# Power.net
KiCad netlist of a schematic drawn in Altium Designer
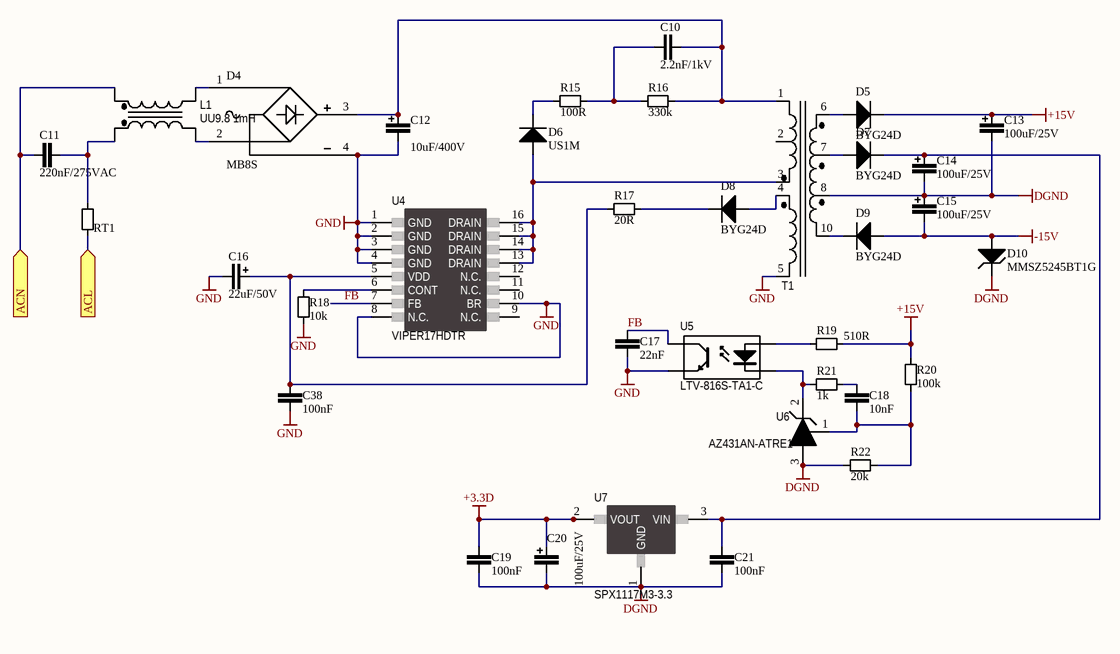
[diagram p0: Power.SchDoc]

(export (version "E")
  (design (tool "Eeschema 10.0.6"))
  (components
    (comp (ref "C10")
      (value "2.2nF/1kV")
      (footprint "GreenBox:1206-C")
      (description "MLCC 2.2nF 10% 1000V X7R 1206")
      (fields (field (name "Comment") "High-Volt Cap") (field (name "PUBLISHER") "GreenBox"))
      (libsource (lib "Capacitor") (part "C21E02N2K3A0"))
    )
    (comp (ref "C11")
      (value "220nF/275VAC")
      (footprint "GreenBox:C-F-C3")
      (description "FILM CAP 220nF 10% 275VAC MPX X2 10mm")
      (fields (field (name "Comment") "FILM Cap") (field (name "PUBLISHER") "GreenBox"))
      (libsource (lib "Capacitor") (part "CXDM220NKAC0"))
    )
    (comp (ref "C12")
      (value "10uF/400V")
      (footprint "GreenBox:C-E-ALU-10X16")
      (description "DIP ECAP 10uF 20% 400V 10X16")
      (fields (field (name "Comment") "ECap") (field (name "PUBLISHER") "GreenBox"))
      (libsource (lib "Capacitor") (part "C3AE010UM2G0"))
    )
    (comp (ref "C13")
      (value "100uF/25V")
      (footprint "GreenBox:C-E-ALU-6.3X11.5")
      (description "DIP ECAP 100uF 20% 25V 6.3X11.5")
      (fields (field (name "Comment") "ECap") (field (name "PUBLISHER") "GreenBox"))
      (libsource (lib "Capacitor") (part "C3AC100UM1E0"))
    )
    (comp (ref "C14")
      (value "100uF/25V")
      (footprint "GreenBox:C-E-ALU-6.3X11.5")
      (description "DIP ECAP 100uF 20% 25V 6.3X11.5")
      (fields (field (name "Comment") "ECap") (field (name "PUBLISHER") "GreenBox"))
      (libsource (lib "Capacitor") (part "C3AC100UM1E0"))
    )
    (comp (ref "C15")
      (value "100uF/25V")
      (footprint "GreenBox:C-E-ALU-6.3X11.5")
      (description "DIP ECAP 100uF 20% 25V 6.3X11.5")
      (fields (field (name "Comment") "ECap") (field (name "PUBLISHER") "GreenBox"))
      (libsource (lib "Capacitor") (part "C3AC100UM1E0"))
    )
    (comp (ref "C16")
      (value "22uF/50V")
      (footprint "GreenBox:C-E-ALU-5X11")
      (description "DIP ECAP 22uF 20% 50V 5X11")
      (fields (field (name "Comment") "ECap") (field (name "PUBLISHER") "GreenBox"))
      (libsource (lib "Capacitor") (part "C3AB022UM1H0"))
    )
    (comp (ref "C17")
      (value "22nF")
      (footprint "GreenBox:0603-C")
      (description "MLCC 22nF 10% 50V X7R 0603")
      (fields (field (name "Comment") "Cap") (field (name "PUBLISHER") "GreenBox"))
      (libsource (lib "Capacitor") (part "C21C022NK1H0"))
    )
    (comp (ref "C18")
      (value "10nF")
      (footprint "GreenBox:0603-C")
      (description "MLCC 10nF 10% 50V X7R 0603")
      (fields (field (name "Comment") "Cap") (field (name "PUBLISHER") "GreenBox"))
      (libsource (lib "Capacitor") (part "C21C010NK1H0"))
    )
    (comp (ref "C19")
      (value "100nF")
      (footprint "GreenBox:0603-C")
      (description "MLCC 100nF 10% 50V X7R 0603")
      (fields (field (name "Comment") "Cap") (field (name "PUBLISHER") "GreenBox"))
      (libsource (lib "Capacitor") (part "C21C100NK1H0"))
    )
    (comp (ref "C20")
      (value "100uF/25V")
      (footprint "GreenBox:C-E-ALU-6.3X11.5")
      (description "DIP ECAP 100uF 20% 25V 6.3X11.5")
      (fields (field (name "Comment") "ECap") (field (name "PUBLISHER") "GreenBox"))
      (libsource (lib "Capacitor") (part "C3AC100UM1E0"))
    )
    (comp (ref "C21")
      (value "100nF")
      (footprint "GreenBox:0603-C")
      (description "MLCC 100nF 10% 50V X7R 0603")
      (fields (field (name "Comment") "Cap") (field (name "PUBLISHER") "GreenBox"))
      (libsource (lib "Capacitor") (part "C21C100NK1H0"))
    )
    (comp (ref "C38")
      (value "100nF")
      (footprint "GreenBox:0603-C")
      (description "MLCC 100nF 10% 50V X7R 0603")
      (fields (field (name "Comment") "Cap") (field (name "PUBLISHER") "GreenBox"))
      (libsource (lib "Capacitor") (part "C21C100NK1H0"))
    )
    (comp (ref "D4")
      (value "MB8S")
      (footprint "GreenBox:MBS-1")
      (description "Bridge Rectifiers MB8S 800V 0.5A")
      (fields (field (name "MANUFACTURER") "ON SEMICONDUCTOR") (field (name "PUBLISHER") "GreenBox"))
      (libsource (lib "Diode_Transistor") (part "DBSAMB8S0000"))
    )
    (comp (ref "D5")
      (value "BYG24D")
      (footprint "GreenBox:DO-214AC")
      (description "Fast Recovery Rectifiers BYG24D Vrrm 200V If 1.5A 140nS")
      (fields (field (name "MANUFACTURER") "VISHAY") (field (name "PUBLISHER") "GreenBox"))
      (libsource (lib "Diode_Transistor") (part "D461BYG24D0V"))
    )
    (comp (ref "D6")
      (value "US1M")
      (footprint "GreenBox:DO-214AC")
      (description "Fast Recovery Rectifiers US1M Vrrm 1000V If 1A 75nS")
      (fields (field (name "PUBLISHER") "GreenBox"))
      (libsource (lib "Diode_Transistor") (part "D461US1M0000"))
    )
    (comp (ref "D7")
      (value "BYG24D")
      (footprint "GreenBox:DO-214AC")
      (description "Fast Recovery Rectifiers BYG24D Vrrm 200V If 1.5A 140nS")
      (fields (field (name "MANUFACTURER") "VISHAY") (field (name "PUBLISHER") "GreenBox"))
      (libsource (lib "Diode_Transistor") (part "D461BYG24D0V"))
    )
    (comp (ref "D8")
      (value "BYG24D")
      (footprint "GreenBox:DO-214AC")
      (description "Fast Recovery Rectifiers BYG24D Vrrm 200V If 1.5A 140nS")
      (fields (field (name "MANUFACTURER") "VISHAY") (field (name "PUBLISHER") "GreenBox"))
      (libsource (lib "Diode_Transistor") (part "D461BYG24D0V"))
    )
    (comp (ref "D9")
      (value "BYG24D")
      (footprint "GreenBox:DO-214AC")
      (description "Fast Recovery Rectifiers BYG24D Vrrm 200V If 1.5A 140nS")
      (fields (field (name "MANUFACTURER") "VISHAY") (field (name "PUBLISHER") "GreenBox"))
      (libsource (lib "Diode_Transistor") (part "D461BYG24D0V"))
    )
    (comp (ref "D10")
      (value "MMSZ5245BT1G")
      (footprint "GreenBox:SOD-123")
      (description "Zener Voltage Regulators MMSZ5245BT1G 15V 0W5")
      (fields (field (name "MANUFACTURER") "ON SEMICONDUCTOR") (field (name "PUBLISHER") "GreenBox"))
      (libsource (lib "Diode_Transistor") (part "D531MSZ5245O"))
    )
    (comp (ref "L1")
      (value "UU9.8 1mH")
      (footprint "GreenBox:UU9_8")
      (description "Common Mode Inductor UU9.8 1mH 1A")
      (fields (field (name "PUBLISHER") "GreenBox"))
      (libsource (lib "Inductor") (part "LCDZUU9801M0"))
    )
    (comp (ref "R15")
      (value "100R")
      (footprint "GreenBox:1206-R")
      (description "SMD Resistor 100R 1% 1/4W 1206 100PPM")
      (fields (field (name "Comment") "Res") (field (name "PUBLISHER") "GreenBox"))
      (libsource (lib "Resistor") (part "R11E100RFDF0"))
    )
    (comp (ref "R16")
      (value "330k")
      (footprint "GreenBox:1206-R")
      (description "SMD Resistor 330k 1% 1/4W 1206 100PPM")
      (fields (field (name "Comment") "Res") (field (name "PUBLISHER") "GreenBox"))
      (libsource (lib "Resistor") (part "R11E330KFDF0"))
    )
    (comp (ref "R17")
      (value "20R")
      (footprint "GreenBox:1206-R")
      (description "SMD Resistor 20R 1% 1/4W 1206 100PPM")
      (fields (field (name "Comment") "Res") (field (name "PUBLISHER") "GreenBox"))
      (libsource (lib "Resistor") (part "R11E020RFDF0"))
    )
    (comp (ref "R18")
      (value "10k")
      (footprint "GreenBox:0603-R")
      (description "SMD Resistor 10k 1% 1/10W 0603 100PPM")
      (fields (field (name "Comment") "Res") (field (name "PUBLISHER") "GreenBox"))
      (libsource (lib "Resistor") (part "R11C010KFBF0"))
    )
    (comp (ref "R19")
      (value "510R")
      (footprint "GreenBox:0603-R")
      (description "SMD Resistor 510R 1% 1/10W 0603 100PPM")
      (fields (field (name "Comment") "Res") (field (name "PUBLISHER") "GreenBox"))
      (libsource (lib "Resistor") (part "R11C510RFBF0"))
    )
    (comp (ref "R20")
      (value "100k")
      (footprint "GreenBox:0603-R")
      (description "SMD Resistor 100k 1% 1/10W 0603 100PPM")
      (fields (field (name "Comment") "Res") (field (name "PUBLISHER") "GreenBox"))
      (libsource (lib "Resistor") (part "R11C100KFBF0"))
    )
    (comp (ref "R21")
      (value "1k")
      (footprint "GreenBox:0603-R")
      (description "SMD Resistor 1k 1% 1/10W 0603 100PPM")
      (fields (field (name "Comment") "Res") (field (name "PUBLISHER") "GreenBox"))
      (libsource (lib "Resistor") (part "R11C001KFBF0"))
    )
    (comp (ref "R22")
      (value "20k")
      (footprint "GreenBox:0603-R")
      (description "SMD Resistor 20k 1% 1/10W 0603 100PPM")
      (fields (field (name "Comment") "Res") (field (name "PUBLISHER") "GreenBox"))
      (libsource (lib "Resistor") (part "R11C020KFBF0"))
    )
    (comp (ref "RT1")
      (value "SY16P")
      (footprint "GreenBox:PTC-16P")
      (description "PTC SY16P")
      (fields (field (name "PUBLISHER") "GreenBox"))
      (libsource (lib "Resistor") (part "RPDZSY16P000"))
    )
    (comp (ref "T1")
      (value "Transformer")
      (footprint "GreenBox:EE13-5+5-Q9")
      (description "Transformer EE13 GREENBOX 16A Auxiliary Power")
      (fields (field (name "PUBLISHER") "GreenBox"))
      (libsource (lib "Transformer") (part "MTD5220050A0"))
    )
    (comp (ref "U4")
      (value "VIPER17HDTR")
      (footprint "GreenBox:SO-16_N")
      (description "Switching Regulator VIPER17HDTR 127kHz")
      (fields (field (name "MANUFACTURER") "STMicroelectronics") (field (name "PUBLISHER") "GreenBox"))
      (libsource (lib "DCDC_LDO") (part "UDS3VIPER17S"))
    )
    (comp (ref "U5")
      (value "LTV-816S-TA1-C")
      (footprint "GreenBox:DIP-4-SMD-OPTO")
      (description "Phototransistor Optocoupler LTV-816S-TA1-C Viso 5000Vrms")
      (fields (field (name "MANUFACTURER") "LITE-ON ELECTRONICS") (field (name "PUBLISHER") "GreenBox"))
      (libsource (lib "Optocoupler") (part "UOSBLTV816SI"))
    )
    (comp (ref "U6")
      (value "AZ431AN-ATRE1")
      (footprint "GreenBox:SOT-23_N")
      (description "Voltage Reference AZ431AN-ATRE1 Vref 2.5V")
      (fields (field (name "MANUFACTURER") "BCD SEMICONDUCTOR") (field (name "PUBLISHER") "GreenBox"))
      (libsource (lib "DCDC_LDO") (part "UV42AZ431ANB"))
    )
    (comp (ref "U7")
      (value "SPX1117M3-3.3")
      (footprint "GreenBox:SOT223_N")
      (description "LDO SPX1117M3-3.3 3V3 800mA")
      (fields (field (name "MANUFACTURER") "SIPEX CORPORATION") (field (name "PUBLISHER") "GreenBox"))
      (libsource (lib "DCDC_LDO") (part "UL4111173V3E"))
    )
  )
  (nets
    (net (code "1") (name "+3.3D") (class "Default")
      (node (ref "C19") (pin "1") (pinfunction "1_1") (pintype "passive"))
      (node (ref "C20") (pin "1") (pinfunction "1_1") (pintype "passive"))
      (node (ref "U7") (pin "2") (pinfunction "VOUT_2") (pintype "passive"))
      (node (ref "U7") (pin "4") (pinfunction "VOUT_4") (pintype "passive"))
    )
    (net (code "2") (name "+15V") (class "Default")
      (node (ref "C13") (pin "1") (pinfunction "1_1") (pintype "passive"))
      (node (ref "D5") (pin "2") (pinfunction "K_2") (pintype "passive"))
      (node (ref "R19") (pin "1") (pinfunction "1_1") (pintype "passive"))
      (node (ref "R20") (pin "2") (pinfunction "2_2") (pintype "passive"))
    )
    (net (code "3") (name "-15V") (class "Default")
      (node (ref "C15") (pin "2") (pinfunction "2_2") (pintype "passive"))
      (node (ref "D10") (pin "1") (pinfunction "A_1") (pintype "passive"))
      (node (ref "D9") (pin "1") (pinfunction "A_1") (pintype "passive"))
    )
    (net (code "4") (name "/ACL") (class "Default")
      (node (ref "RT1") (pin "1") (pinfunction "1_1") (pintype "passive"))
    )
    (net (code "5") (name "/ACN") (class "Default")
      (node (ref "C11") (pin "1") (pinfunction "1_1") (pintype "passive"))
      (node (ref "L1") (pin "3") (pinfunction "Sec+_3") (pintype "passive"))
    )
    (net (code "6") (name "/FB") (class "Default")
      (node (ref "C17") (pin "1") (pinfunction "1_1") (pintype "passive"))
      (node (ref "U4") (pin "7") (pinfunction "FB_7") (pintype "passive"))
      (node (ref "U5") (pin "4") (pinfunction "C_4") (pintype "passive"))
    )
    (net (code "7") (name "DGND") (class "Default")
      (node (ref "C13") (pin "2") (pinfunction "2_2") (pintype "passive"))
      (node (ref "C14") (pin "2") (pinfunction "2_2") (pintype "passive"))
      (node (ref "C15") (pin "1") (pinfunction "1_1") (pintype "passive"))
      (node (ref "C19") (pin "2") (pinfunction "2_2") (pintype "passive"))
      (node (ref "C20") (pin "2") (pinfunction "2_2") (pintype "passive"))
      (node (ref "C21") (pin "1") (pinfunction "1_1") (pintype "passive"))
      (node (ref "D10") (pin "2") (pinfunction "K_2") (pintype "passive"))
      (node (ref "R22") (pin "2") (pinfunction "2_2") (pintype "passive"))
      (node (ref "T1") (pin "8") (pinfunction "8_8") (pintype "passive"))
      (node (ref "U6") (pin "3") (pinfunction "IN-_3") (pintype "passive"))
      (node (ref "U7") (pin "1") (pinfunction "GND_1") (pintype "passive"))
    )
    (net (code "8") (name "GND") (class "Default")
      (node (ref "C12") (pin "2") (pinfunction "2_2") (pintype "passive"))
      (node (ref "C16") (pin "2") (pinfunction "2_2") (pintype "passive"))
      (node (ref "C17") (pin "2") (pinfunction "2_2") (pintype "passive"))
      (node (ref "C38") (pin "2") (pinfunction "2_2") (pintype "passive"))
      (node (ref "D4") (pin "4") (pinfunction "-_4") (pintype "passive"))
      (node (ref "R18") (pin "2") (pinfunction "2_2") (pintype "passive"))
      (node (ref "T1") (pin "5") (pinfunction "5_5") (pintype "passive"))
      (node (ref "U4") (pin "1") (pinfunction "GND_1") (pintype "passive"))
      (node (ref "U4") (pin "10") (pinfunction "BR_10") (pintype "passive"))
      (node (ref "U4") (pin "2") (pinfunction "GND_2") (pintype "passive"))
      (node (ref "U4") (pin "3") (pinfunction "GND_3") (pintype "passive"))
      (node (ref "U4") (pin "4") (pinfunction "GND_4") (pintype "passive"))
      (node (ref "U4") (pin "8") (pinfunction "N.C._8") (pintype "passive"))
      (node (ref "U5") (pin "3") (pinfunction "E_3") (pintype "passive"))
    )
    (net (code "9") (name "Net-(C10-Pad1)") (class "Default")
      (node (ref "C10") (pin "1") (pinfunction "1_1") (pintype "passive"))
      (node (ref "R15") (pin "2") (pinfunction "2_2") (pintype "passive"))
      (node (ref "R16") (pin "2") (pinfunction "2_2") (pintype "passive"))
    )
    (net (code "10") (name "Net-(C18-Pad1)") (class "Default")
      (node (ref "C18") (pin "1") (pinfunction "1_1") (pintype "passive"))
      (node (ref "R21") (pin "2") (pinfunction "2_2") (pintype "passive"))
    )
    (net (code "11") (name "Net-(D4-+)") (class "Default")
      (node (ref "C10") (pin "2") (pinfunction "2_2") (pintype "passive"))
      (node (ref "C12") (pin "1") (pinfunction "1_1") (pintype "passive"))
      (node (ref "D4") (pin "3") (pinfunction "+_3") (pintype "passive"))
      (node (ref "R16") (pin "1") (pinfunction "1_1") (pintype "passive"))
      (node (ref "T1") (pin "1") (pinfunction "1_1") (pintype "passive"))
    )
    (net (code "12") (name "Net-(D5-A)") (class "Default")
      (node (ref "D5") (pin "1") (pinfunction "A_1") (pintype "passive"))
      (node (ref "T1") (pin "6") (pinfunction "6_6") (pintype "passive"))
    )
    (net (code "13") (name "Net-(D6-A)") (class "Default")
      (node (ref "D6") (pin "1") (pinfunction "A_1") (pintype "passive"))
      (node (ref "T1") (pin "3") (pinfunction "3_3") (pintype "passive"))
      (node (ref "U4") (pin "13") (pinfunction "DRAIN_13") (pintype "passive"))
      (node (ref "U4") (pin "14") (pinfunction "DRAIN_14") (pintype "passive"))
      (node (ref "U4") (pin "15") (pinfunction "DRAIN_15") (pintype "passive"))
      (node (ref "U4") (pin "16") (pinfunction "DRAIN_16") (pintype "passive"))
    )
    (net (code "14") (name "Net-(D6-K)") (class "Default")
      (node (ref "D6") (pin "2") (pinfunction "K_2") (pintype "passive"))
      (node (ref "R15") (pin "1") (pinfunction "1_1") (pintype "passive"))
    )
    (net (code "15") (name "Net-(D7-A)") (class "Default")
      (node (ref "D7") (pin "1") (pinfunction "A_1") (pintype "passive"))
      (node (ref "T1") (pin "7") (pinfunction "7_7") (pintype "passive"))
    )
    (net (code "16") (name "Net-(D7-K)") (class "Default")
      (node (ref "C14") (pin "1") (pinfunction "1_1") (pintype "passive"))
      (node (ref "C21") (pin "2") (pinfunction "2_2") (pintype "passive"))
      (node (ref "D7") (pin "2") (pinfunction "K_2") (pintype "passive"))
      (node (ref "U7") (pin "3") (pinfunction "VIN_3") (pintype "passive"))
    )
    (net (code "17") (name "Net-(D8-A)") (class "Default")
      (node (ref "D8") (pin "1") (pinfunction "A_1") (pintype "passive"))
      (node (ref "T1") (pin "4") (pinfunction "4_4") (pintype "passive"))
    )
    (net (code "18") (name "Net-(D8-K)") (class "Default")
      (node (ref "D8") (pin "2") (pinfunction "K_2") (pintype "passive"))
      (node (ref "R17") (pin "2") (pinfunction "2_2") (pintype "passive"))
    )
    (net (code "19") (name "Net-(D9-K)") (class "Default")
      (node (ref "D9") (pin "2") (pinfunction "K_2") (pintype "passive"))
      (node (ref "T1") (pin "10") (pinfunction "10_10") (pintype "passive"))
    )
    (net (code "20") (name "Net-(L1-Pri+)") (class "Default")
      (node (ref "C11") (pin "2") (pinfunction "2_2") (pintype "passive"))
      (node (ref "L1") (pin "1") (pinfunction "Pri+_1") (pintype "passive"))
      (node (ref "RT1") (pin "2") (pinfunction "2_2") (pintype "passive"))
    )
    (net (code "21") (name "Net-(L1-Pri-)") (class "Default")
      (node (ref "D4") (pin "2") (pinfunction "AC_2") (pintype "passive"))
      (node (ref "L1") (pin "2") (pinfunction "Pri-_2") (pintype "passive"))
    )
    (net (code "22") (name "Net-(L1-Sec-)") (class "Default")
      (node (ref "D4") (pin "1") (pinfunction "AC_1") (pintype "passive"))
      (node (ref "L1") (pin "4") (pinfunction "Sec-_4") (pintype "passive"))
    )
    (net (code "23") (name "Net-(U4-CONT)") (class "Default")
      (node (ref "R18") (pin "1") (pinfunction "1_1") (pintype "passive"))
      (node (ref "U4") (pin "6") (pinfunction "CONT_6") (pintype "passive"))
    )
    (net (code "24") (name "Net-(U4-VDD)") (class "Default")
      (node (ref "C16") (pin "1") (pinfunction "1_1") (pintype "passive"))
      (node (ref "C38") (pin "1") (pinfunction "1_1") (pintype "passive"))
      (node (ref "R17") (pin "1") (pinfunction "1_1") (pintype "passive"))
      (node (ref "U4") (pin "5") (pinfunction "VDD_5") (pintype "passive"))
    )
    (net (code "25") (name "Net-(U5-A)") (class "Default")
      (node (ref "R19") (pin "2") (pinfunction "2_2") (pintype "passive"))
      (node (ref "U5") (pin "1") (pinfunction "A_1") (pintype "passive"))
    )
    (net (code "26") (name "Net-(U5-K)") (class "Default")
      (node (ref "R21") (pin "1") (pinfunction "1_1") (pintype "passive"))
      (node (ref "U5") (pin "2") (pinfunction "K_2") (pintype "passive"))
      (node (ref "U6") (pin "2") (pinfunction "IN+_2") (pintype "passive"))
    )
    (net (code "27") (name "Net-(U6-OUT)") (class "Default")
      (node (ref "C18") (pin "2") (pinfunction "2_2") (pintype "passive"))
      (node (ref "R20") (pin "1") (pinfunction "1_1") (pintype "passive"))
      (node (ref "R22") (pin "1") (pinfunction "1_1") (pintype "passive"))
      (node (ref "U6") (pin "1") (pinfunction "OUT_1") (pintype "passive"))
    )
    (net (code "28") (name "unconnected-(T1-Pad2)") (class "Default")
      (node (ref "T1") (pin "2") (pinfunction "2_2") (pintype "passive"))
    )
    (net (code "29") (name "unconnected-(U4-N.C.-Pad9)") (class "Default")
      (node (ref "U4") (pin "9") (pinfunction "N.C._9") (pintype "passive"))
    )
    (net (code "30") (name "unconnected-(U4-N.C.-Pad11)") (class "Default")
      (node (ref "U4") (pin "11") (pinfunction "N.C._11") (pintype "passive"))
    )
    (net (code "31") (name "unconnected-(U4-N.C.-Pad12)") (class "Default")
      (node (ref "U4") (pin "12") (pinfunction "N.C._12") (pintype "passive"))
    )
  )
)
